# Protoboard.net
KiCad netlist of a schematic drawn in EAGLE
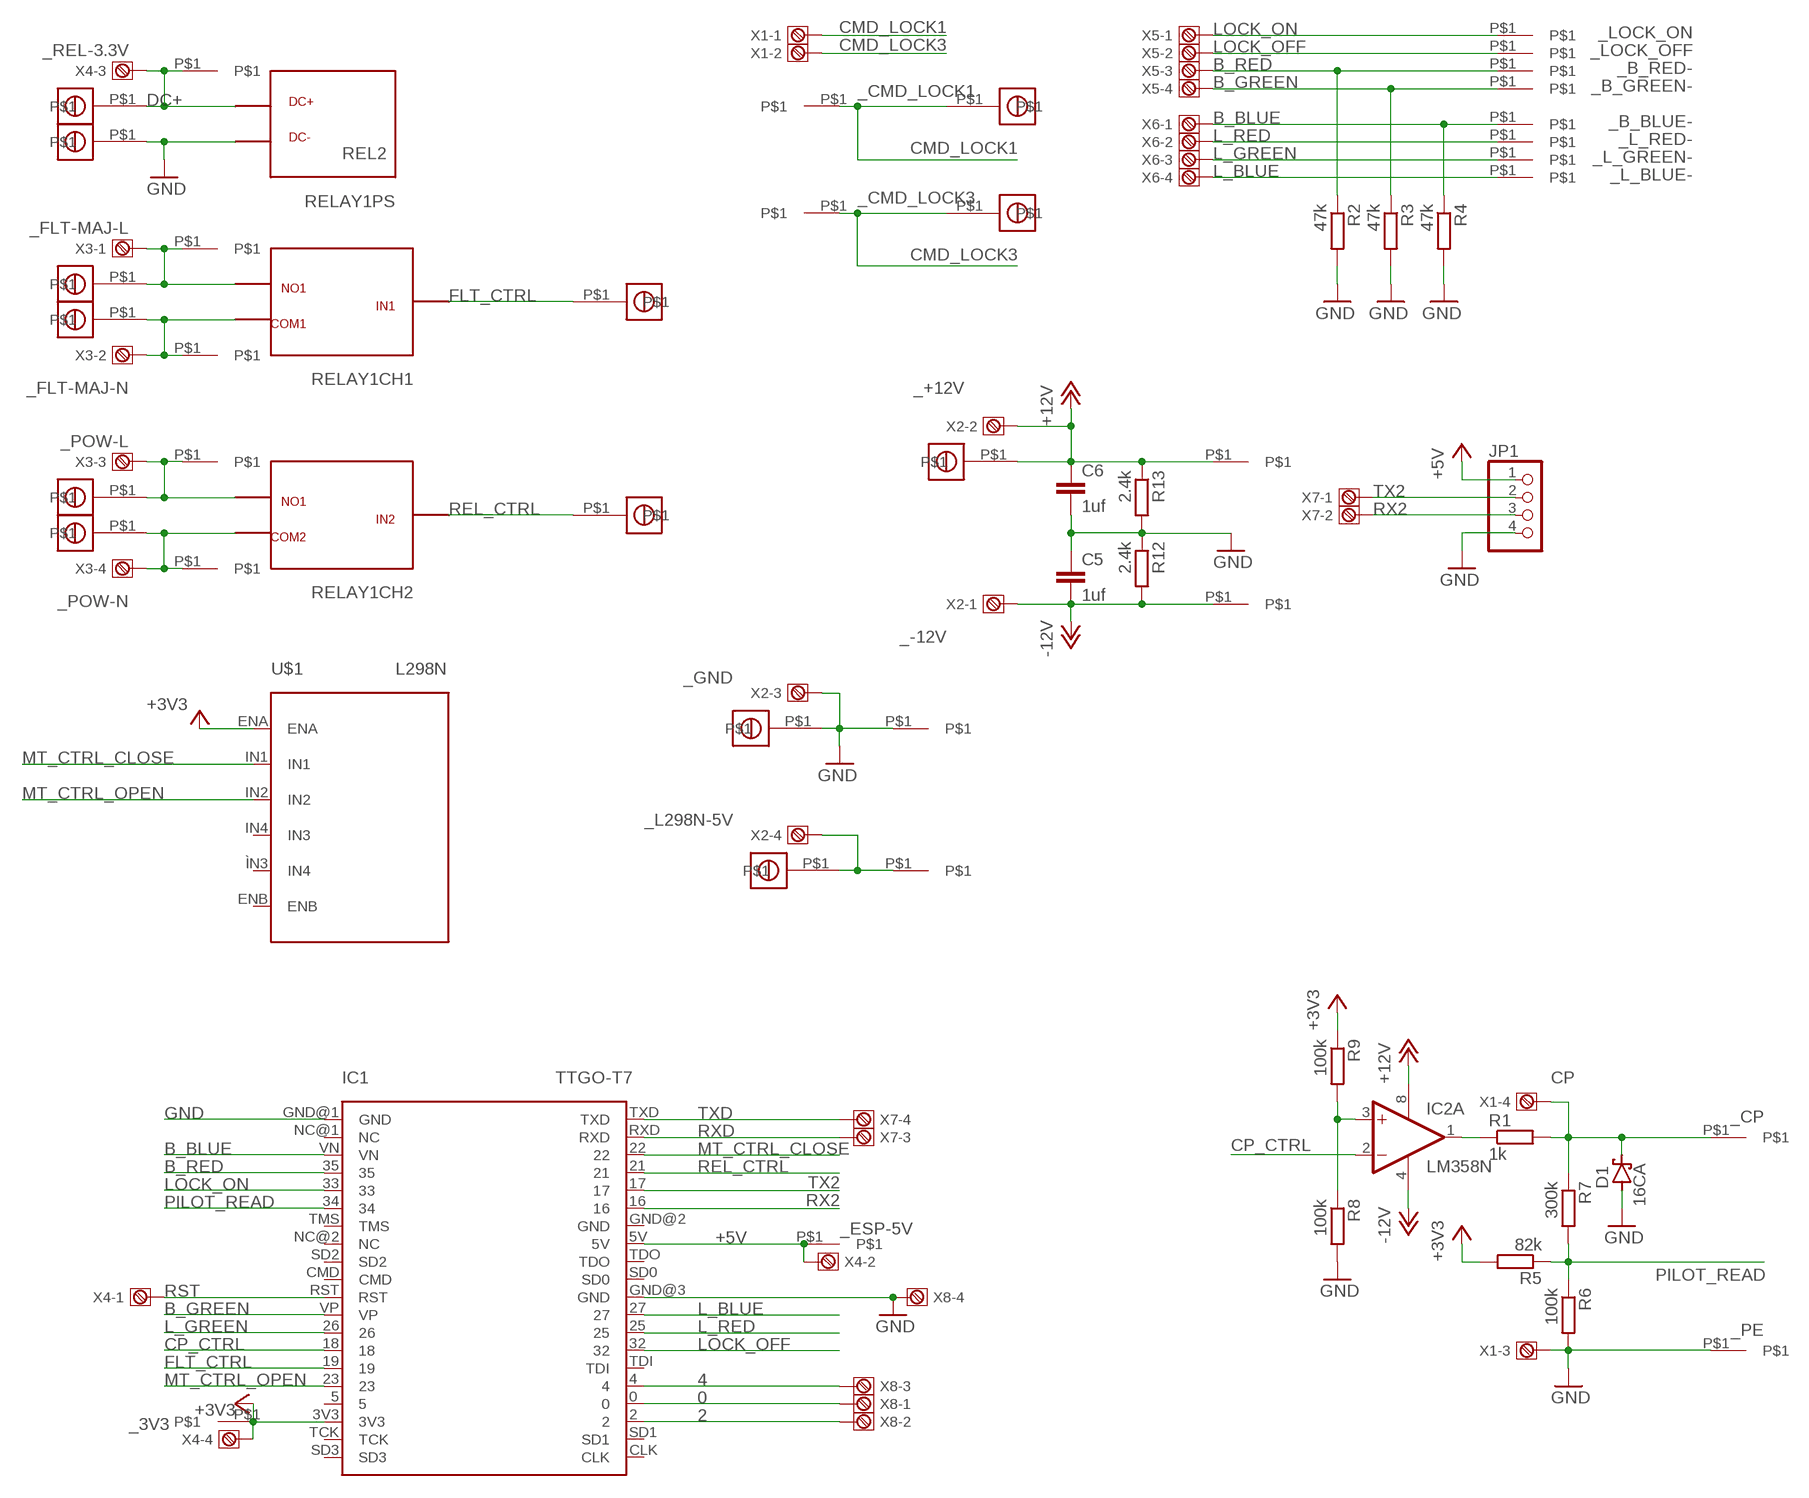
[diagram p0: schematic, sheet 1, part 1 of 2]
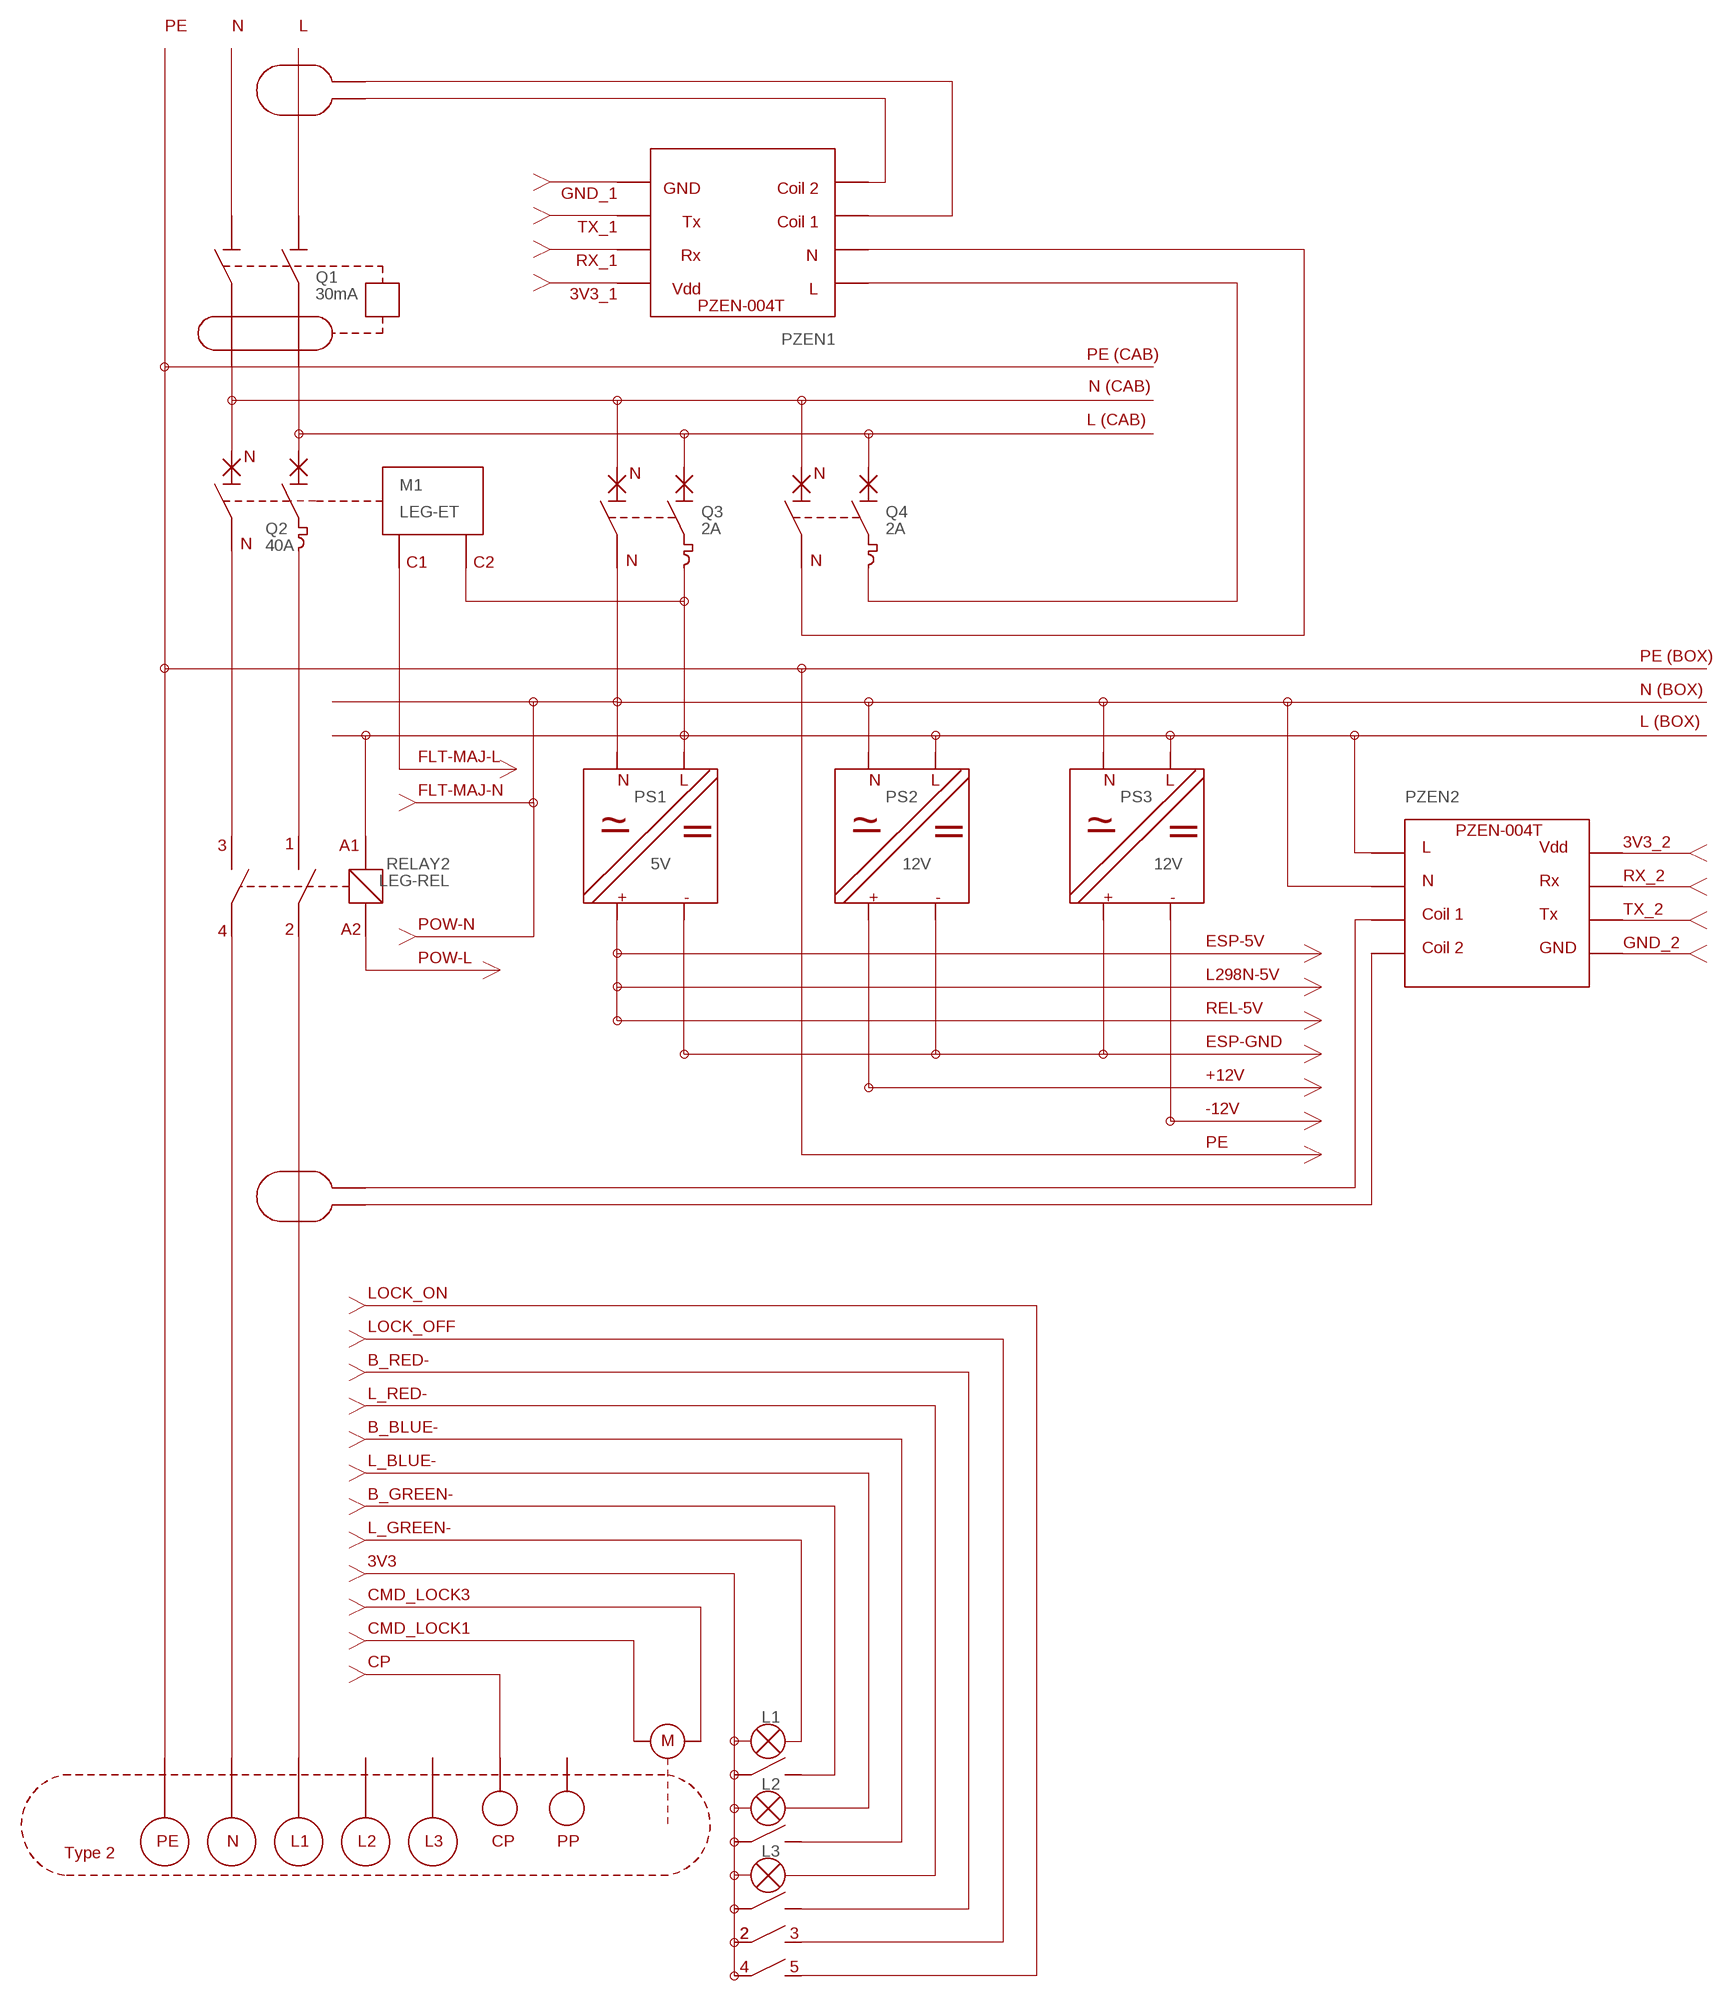
[diagram p1: schematic, sheet 1, part 2 of 2]

(export (version "E")
  (design (tool "Eeschema 10.0.6"))
  (components
    (comp (ref "5V")
      (value "BORNIER")
      (footprint "eagle-import:BORNIER")
      (libsource (lib "eagle-import") (part "BORNIER"))
    )
    (comp (ref "12V")
      (value "BORNIER")
      (footprint "eagle-import:BORNIER")
      (libsource (lib "eagle-import") (part "BORNIER"))
    )
    (comp (ref "C5")
      (value "1uf")
      (footprint "eagle-import:C050-025X075")
      (libsource (lib "eagle-import") (part "C-EU050-025X075"))
    )
    (comp (ref "C6")
      (value "1uf")
      (footprint "eagle-import:C050-025X075")
      (libsource (lib "eagle-import") (part "C-EU050-025X075"))
    )
    (comp (ref "D1")
      (value "16CA")
      (footprint "eagle-import:C1702-15")
      (libsource (lib "eagle-import") (part "P6KEXXA"))
    )
    (comp (ref "DC+")
      (value "BORNIER")
      (footprint "eagle-import:BORNIER")
      (libsource (lib "eagle-import") (part "BORNIER"))
    )
    (comp (ref "DC-")
      (value "BORNIER")
      (footprint "eagle-import:BORNIER")
      (libsource (lib "eagle-import") (part "BORNIER"))
    )
    (comp (ref "FLT-L")
      (value "BORNIER")
      (footprint "eagle-import:BORNIER")
      (libsource (lib "eagle-import") (part "BORNIER"))
    )
    (comp (ref "FLT-N")
      (value "BORNIER")
      (footprint "eagle-import:BORNIER")
      (libsource (lib "eagle-import") (part "BORNIER"))
    )
    (comp (ref "GND")
      (value "BORNIER")
      (footprint "eagle-import:BORNIER")
      (libsource (lib "eagle-import") (part "BORNIER"))
    )
    (comp (ref "IC1")
      (value "TTGO-T7")
      (footprint "eagle-import:TTGO-T7")
      (libsource (lib "eagle-import") (part "TTGO-T7"))
    )
    (comp (ref "IC2")
      (value "LM358N")
      (footprint "eagle-import:DIL08")
      (libsource (lib "eagle-import") (part "LM358N"))
    )
    (comp (ref "IN1")
      (value "BORNIER")
      (footprint "eagle-import:BORNIER")
      (libsource (lib "eagle-import") (part "BORNIER"))
    )
    (comp (ref "IN2")
      (value "BORNIER")
      (footprint "eagle-import:BORNIER")
      (libsource (lib "eagle-import") (part "BORNIER"))
    )
    (comp (ref "JP1")
      (value "PINHD-1X4")
      (footprint "eagle-import:1X04")
      (libsource (lib "eagle-import") (part "PINHD-1X4"))
    )
    (comp (ref "MT1")
      (value "BORNIER")
      (footprint "eagle-import:BORNIER")
      (libsource (lib "eagle-import") (part "BORNIER"))
    )
    (comp (ref "MT2")
      (value "BORNIER")
      (footprint "eagle-import:BORNIER")
      (libsource (lib "eagle-import") (part "BORNIER"))
    )
    (comp (ref "POW-L")
      (value "BORNIER")
      (footprint "eagle-import:BORNIER")
      (libsource (lib "eagle-import") (part "BORNIER"))
    )
    (comp (ref "POW-N")
      (value "BORNIER")
      (footprint "eagle-import:BORNIER")
      (libsource (lib "eagle-import") (part "BORNIER"))
    )
    (comp (ref "R1")
      (value "1k")
      (footprint "eagle-import:0207_10")
      (libsource (lib "eagle-import") (part "R-EU_0207/10"))
    )
    (comp (ref "R2")
      (value "47k")
      (footprint "eagle-import:0207_10")
      (libsource (lib "eagle-import") (part "R-EU_0207/10"))
    )
    (comp (ref "R3")
      (value "47k")
      (footprint "eagle-import:0207_10")
      (libsource (lib "eagle-import") (part "R-EU_0207/10"))
    )
    (comp (ref "R4")
      (value "47k")
      (footprint "eagle-import:0207_10")
      (libsource (lib "eagle-import") (part "R-EU_0207/10"))
    )
    (comp (ref "R5")
      (value "82k")
      (footprint "eagle-import:0207_10")
      (libsource (lib "eagle-import") (part "R-EU_0207/10"))
    )
    (comp (ref "R6")
      (value "100k")
      (footprint "eagle-import:0207_10")
      (libsource (lib "eagle-import") (part "R-EU_0207/10"))
    )
    (comp (ref "R7")
      (value "300k")
      (footprint "eagle-import:0207_10")
      (libsource (lib "eagle-import") (part "R-EU_0207/10"))
    )
    (comp (ref "R8")
      (value "100k")
      (footprint "eagle-import:0207_10")
      (libsource (lib "eagle-import") (part "R-EU_0207/10"))
    )
    (comp (ref "R9")
      (value "100k")
      (footprint "eagle-import:0207_10")
      (libsource (lib "eagle-import") (part "R-EU_0207/10"))
    )
    (comp (ref "R12")
      (value "2.4k")
      (footprint "eagle-import:0207_10")
      (libsource (lib "eagle-import") (part "R-EU_0207/10"))
    )
    (comp (ref "R13")
      (value "2.4k")
      (footprint "eagle-import:0207_10")
      (libsource (lib "eagle-import") (part "R-EU_0207/10"))
    )
    (comp (ref "RELAY1")
      (value "REL2")
      (footprint "eagle-import:REL2")
      (libsource (lib "eagle-import") (part "REL2"))
    )
    (comp (ref "U$1")
      (value "L298N")
      (footprint "eagle-import:L298N")
      (libsource (lib "eagle-import") (part "L298N"))
    )
    (comp (ref "X1")
      (value "1727036")
      (footprint "eagle-import:1727036")
      (fields (field (name "MF") "FARNELL"))
      (libsource (lib "eagle-import") (part "1727036"))
    )
    (comp (ref "X2")
      (value "1727036")
      (footprint "eagle-import:1727036")
      (fields (field (name "MF") "FARNELL"))
      (libsource (lib "eagle-import") (part "1727036"))
    )
    (comp (ref "X3")
      (value "1727036")
      (footprint "eagle-import:1727036")
      (fields (field (name "MF") "FARNELL"))
      (libsource (lib "eagle-import") (part "1727036"))
    )
    (comp (ref "X4")
      (value "1727036")
      (footprint "eagle-import:1727036")
      (fields (field (name "MF") "FARNELL"))
      (libsource (lib "eagle-import") (part "1727036"))
    )
    (comp (ref "X5")
      (value "1727036")
      (footprint "eagle-import:1727036")
      (fields (field (name "MF") "FARNELL"))
      (libsource (lib "eagle-import") (part "1727036"))
    )
    (comp (ref "X6")
      (value "1727036")
      (footprint "eagle-import:1727036")
      (fields (field (name "MF") "FARNELL"))
      (libsource (lib "eagle-import") (part "1727036"))
    )
    (comp (ref "X7")
      (value "1727036")
      (footprint "eagle-import:1727036")
      (fields (field (name "MF") "FARNELL"))
      (libsource (lib "eagle-import") (part "1727036"))
    )
    (comp (ref "X8")
      (value "1727036")
      (footprint "eagle-import:1727036")
      (fields (field (name "MF") "FARNELL"))
      (libsource (lib "eagle-import") (part "1727036"))
    )
    (comp (ref "_+12V")
      (value "PIN")
      (footprint "eagle-import:PIN")
      (libsource (lib "eagle-import") (part "PIN"))
    )
    (comp (ref "_-12V")
      (value "PIN")
      (footprint "eagle-import:PIN")
      (libsource (lib "eagle-import") (part "PIN"))
    )
    (comp (ref "_3V3")
      (value "PIN")
      (footprint "eagle-import:PIN")
      (libsource (lib "eagle-import") (part "PIN"))
    )
    (comp (ref "_B_BLUE-")
      (value "PIN")
      (footprint "eagle-import:PIN")
      (libsource (lib "eagle-import") (part "PIN"))
    )
    (comp (ref "_B_GREEN-")
      (value "PIN")
      (footprint "eagle-import:PIN")
      (libsource (lib "eagle-import") (part "PIN"))
    )
    (comp (ref "_B_RED-")
      (value "PIN")
      (footprint "eagle-import:PIN")
      (libsource (lib "eagle-import") (part "PIN"))
    )
    (comp (ref "_CMD_LOCK1")
      (value "PIN")
      (footprint "eagle-import:PIN")
      (libsource (lib "eagle-import") (part "PIN"))
    )
    (comp (ref "_CMD_LOCK3")
      (value "PIN")
      (footprint "eagle-import:PIN")
      (libsource (lib "eagle-import") (part "PIN"))
    )
    (comp (ref "_CP")
      (value "PIN")
      (footprint "eagle-import:PIN")
      (libsource (lib "eagle-import") (part "PIN"))
    )
    (comp (ref "_ESP-5V")
      (value "PIN")
      (footprint "eagle-import:PIN")
      (libsource (lib "eagle-import") (part "PIN"))
    )
    (comp (ref "_FLT-MAJ-L")
      (value "PIN")
      (footprint "eagle-import:PIN")
      (libsource (lib "eagle-import") (part "PIN"))
    )
    (comp (ref "_FLT-MAJ-N")
      (value "PIN")
      (footprint "eagle-import:PIN")
      (libsource (lib "eagle-import") (part "PIN"))
    )
    (comp (ref "_GND")
      (value "PIN")
      (footprint "eagle-import:PIN")
      (libsource (lib "eagle-import") (part "PIN"))
    )
    (comp (ref "_L298N-5V")
      (value "PIN")
      (footprint "eagle-import:PIN")
      (libsource (lib "eagle-import") (part "PIN"))
    )
    (comp (ref "_LOCK_OFF")
      (value "PIN")
      (footprint "eagle-import:PIN")
      (libsource (lib "eagle-import") (part "PIN"))
    )
    (comp (ref "_LOCK_ON")
      (value "PIN")
      (footprint "eagle-import:PIN")
      (libsource (lib "eagle-import") (part "PIN"))
    )
    (comp (ref "_L_BLUE-")
      (value "PIN")
      (footprint "eagle-import:PIN")
      (libsource (lib "eagle-import") (part "PIN"))
    )
    (comp (ref "_L_GREEN-")
      (value "PIN")
      (footprint "eagle-import:PIN")
      (libsource (lib "eagle-import") (part "PIN"))
    )
    (comp (ref "_L_RED-")
      (value "PIN")
      (footprint "eagle-import:PIN")
      (libsource (lib "eagle-import") (part "PIN"))
    )
    (comp (ref "_PE")
      (value "PIN")
      (footprint "eagle-import:PIN")
      (libsource (lib "eagle-import") (part "PIN"))
    )
    (comp (ref "_POW-L")
      (value "PIN")
      (footprint "eagle-import:PIN")
      (libsource (lib "eagle-import") (part "PIN"))
    )
    (comp (ref "_POW-N")
      (value "PIN")
      (footprint "eagle-import:PIN")
      (libsource (lib "eagle-import") (part "PIN"))
    )
    (comp (ref "_REL-3.3V")
      (value "PIN")
      (footprint "eagle-import:PIN")
      (libsource (lib "eagle-import") (part "PIN"))
    )
  )
  (nets
    (net (code "1") (name "+3V3") (class "Default")
      (node (ref "IC1") (pin "3V3") (pinfunction "3V3_3V3") (pintype "bidirectional"))
      (node (ref "R5") (pin "2") (pinfunction "2_2") (pintype "passive"))
      (node (ref "R9") (pin "1") (pinfunction "1_1") (pintype "passive"))
      (node (ref "U$1") (pin "ENA") (pinfunction "ENA_ENA") (pintype "bidirectional"))
      (node (ref "X4") (pin "4") (pinfunction "1_4") (pintype "passive"))
      (node (ref "_3V3") (pin "P$1") (pinfunction "P$1_P$1") (pintype "bidirectional"))
    )
    (net (code "2") (name "+5V") (class "Default")
      (node (ref "IC1") (pin "5V") (pinfunction "5V_5V") (pintype "bidirectional"))
      (node (ref "JP1") (pin "1") (pinfunction "1_1") (pintype "passive"))
      (node (ref "X4") (pin "2") (pinfunction "1_2") (pintype "passive"))
      (node (ref "_ESP-5V") (pin "P$1") (pinfunction "P$1_P$1") (pintype "bidirectional"))
    )
    (net (code "3") (name "+12V") (class "Default")
      (node (ref "12V") (pin "P$1") (pinfunction "P$1_P$1") (pintype "bidirectional"))
      (node (ref "C6") (pin "1") (pinfunction "1_1") (pintype "passive"))
      (node (ref "IC2") (pin "8") (pinfunction "V+_8") (pintype "power_in"))
      (node (ref "R13") (pin "1") (pinfunction "1_1") (pintype "passive"))
      (node (ref "X2") (pin "2") (pinfunction "1_2") (pintype "passive"))
      (node (ref "_+12V") (pin "P$1") (pinfunction "P$1_P$1") (pintype "bidirectional"))
    )
    (net (code "4") (name "-12V") (class "Default")
      (node (ref "C5") (pin "2") (pinfunction "2_2") (pintype "passive"))
      (node (ref "IC2") (pin "4") (pinfunction "V-_4") (pintype "power_in"))
      (node (ref "R12") (pin "2") (pinfunction "2_2") (pintype "passive"))
      (node (ref "X2") (pin "1") (pinfunction "1_1") (pintype "passive"))
      (node (ref "_-12V") (pin "P$1") (pinfunction "P$1_P$1") (pintype "bidirectional"))
    )
    (net (code "5") (name "/0") (class "Default")
      (node (ref "IC1") (pin "0") (pinfunction "0_0") (pintype "bidirectional"))
      (node (ref "X8") (pin "1") (pinfunction "1_1") (pintype "passive"))
    )
    (net (code "6") (name "/2") (class "Default")
      (node (ref "IC1") (pin "2") (pinfunction "2_2") (pintype "bidirectional"))
      (node (ref "X8") (pin "2") (pinfunction "1_2") (pintype "passive"))
    )
    (net (code "7") (name "/4") (class "Default")
      (node (ref "IC1") (pin "4") (pinfunction "4_4") (pintype "bidirectional"))
      (node (ref "X8") (pin "3") (pinfunction "1_3") (pintype "passive"))
    )
    (net (code "8") (name "/B_BLUE") (class "Default")
      (node (ref "IC1") (pin "VN") (pinfunction "VN_VN") (pintype "bidirectional"))
      (node (ref "R4") (pin "1") (pinfunction "1_1") (pintype "passive"))
      (node (ref "X6") (pin "1") (pinfunction "1_1") (pintype "passive"))
      (node (ref "_B_BLUE-") (pin "P$1") (pinfunction "P$1_P$1") (pintype "bidirectional"))
    )
    (net (code "9") (name "/B_GREEN") (class "Default")
      (node (ref "IC1") (pin "VP") (pinfunction "VP_VP") (pintype "bidirectional"))
      (node (ref "R3") (pin "1") (pinfunction "1_1") (pintype "passive"))
      (node (ref "X5") (pin "4") (pinfunction "1_4") (pintype "passive"))
      (node (ref "_B_GREEN-") (pin "P$1") (pinfunction "P$1_P$1") (pintype "bidirectional"))
    )
    (net (code "10") (name "/B_RED") (class "Default")
      (node (ref "IC1") (pin "35") (pinfunction "35_35") (pintype "bidirectional"))
      (node (ref "R2") (pin "1") (pinfunction "1_1") (pintype "passive"))
      (node (ref "X5") (pin "3") (pinfunction "1_3") (pintype "passive"))
      (node (ref "_B_RED-") (pin "P$1") (pinfunction "P$1_P$1") (pintype "bidirectional"))
    )
    (net (code "11") (name "/CMD_LOCK1") (class "Default")
      (node (ref "MT2") (pin "P$1") (pinfunction "P$1_P$1") (pintype "bidirectional"))
      (node (ref "X1") (pin "2") (pinfunction "1_2") (pintype "passive"))
      (node (ref "_CMD_LOCK1") (pin "P$1") (pinfunction "P$1_P$1") (pintype "bidirectional"))
    )
    (net (code "12") (name "/CMD_LOCK3") (class "Default")
      (node (ref "MT1") (pin "P$1") (pinfunction "P$1_P$1") (pintype "bidirectional"))
      (node (ref "X1") (pin "1") (pinfunction "1_1") (pintype "passive"))
      (node (ref "_CMD_LOCK3") (pin "P$1") (pinfunction "P$1_P$1") (pintype "bidirectional"))
    )
    (net (code "13") (name "/CP") (class "Default")
      (node (ref "D1") (pin "C") (pinfunction "C_C") (pintype "passive"))
      (node (ref "R1") (pin "2") (pinfunction "2_2") (pintype "passive"))
      (node (ref "R7") (pin "1") (pinfunction "1_1") (pintype "passive"))
      (node (ref "X1") (pin "4") (pinfunction "1_4") (pintype "passive"))
      (node (ref "_CP") (pin "P$1") (pinfunction "P$1_P$1") (pintype "bidirectional"))
    )
    (net (code "14") (name "/CP_CTRL") (class "Default")
      (node (ref "IC1") (pin "18") (pinfunction "18_18") (pintype "bidirectional"))
      (node (ref "IC2") (pin "2") (pinfunction "-IN_2") (pintype "input"))
    )
    (net (code "15") (name "/DC+") (class "Default")
      (node (ref "DC+") (pin "P$1") (pinfunction "P$1_P$1") (pintype "bidirectional"))
      (node (ref "X4") (pin "3") (pinfunction "1_3") (pintype "passive"))
      (node (ref "_REL-3.3V") (pin "P$1") (pinfunction "P$1_P$1") (pintype "bidirectional"))
    )
    (net (code "16") (name "/FLT_CTRL") (class "Default")
      (node (ref "IC1") (pin "19") (pinfunction "19_19") (pintype "bidirectional"))
      (node (ref "IN1") (pin "P$1") (pinfunction "P$1_P$1") (pintype "bidirectional"))
    )
    (net (code "17") (name "/LOCK_OFF") (class "Default")
      (node (ref "IC1") (pin "32") (pinfunction "32_32") (pintype "bidirectional"))
      (node (ref "X5") (pin "2") (pinfunction "1_2") (pintype "passive"))
      (node (ref "_LOCK_OFF") (pin "P$1") (pinfunction "P$1_P$1") (pintype "bidirectional"))
    )
    (net (code "18") (name "/LOCK_ON") (class "Default")
      (node (ref "IC1") (pin "33") (pinfunction "33_33") (pintype "bidirectional"))
      (node (ref "X5") (pin "1") (pinfunction "1_1") (pintype "passive"))
      (node (ref "_LOCK_ON") (pin "P$1") (pinfunction "P$1_P$1") (pintype "bidirectional"))
    )
    (net (code "19") (name "/L_BLUE") (class "Default")
      (node (ref "IC1") (pin "27") (pinfunction "27_27") (pintype "bidirectional"))
      (node (ref "X6") (pin "4") (pinfunction "1_4") (pintype "passive"))
      (node (ref "_L_BLUE-") (pin "P$1") (pinfunction "P$1_P$1") (pintype "bidirectional"))
    )
    (net (code "20") (name "/L_GREEN") (class "Default")
      (node (ref "IC1") (pin "26") (pinfunction "26_26") (pintype "bidirectional"))
      (node (ref "X6") (pin "3") (pinfunction "1_3") (pintype "passive"))
      (node (ref "_L_GREEN-") (pin "P$1") (pinfunction "P$1_P$1") (pintype "bidirectional"))
    )
    (net (code "21") (name "/L_RED") (class "Default")
      (node (ref "IC1") (pin "25") (pinfunction "25_25") (pintype "bidirectional"))
      (node (ref "X6") (pin "2") (pinfunction "1_2") (pintype "passive"))
      (node (ref "_L_RED-") (pin "P$1") (pinfunction "P$1_P$1") (pintype "bidirectional"))
    )
    (net (code "22") (name "/MT_CTRL_CLOSE") (class "Default")
      (node (ref "IC1") (pin "22") (pinfunction "22_22") (pintype "bidirectional"))
      (node (ref "U$1") (pin "IN1") (pinfunction "IN1_IN1") (pintype "bidirectional"))
    )
    (net (code "23") (name "/MT_CTRL_OPEN") (class "Default")
      (node (ref "IC1") (pin "23") (pinfunction "23_23") (pintype "bidirectional"))
      (node (ref "U$1") (pin "IN2") (pinfunction "IN2_IN2") (pintype "bidirectional"))
    )
    (net (code "24") (name "/PILOT_READ") (class "Default")
      (node (ref "IC1") (pin "34") (pinfunction "34_34") (pintype "bidirectional"))
      (node (ref "R5") (pin "1") (pinfunction "1_1") (pintype "passive"))
      (node (ref "R6") (pin "1") (pinfunction "1_1") (pintype "passive"))
      (node (ref "R7") (pin "2") (pinfunction "2_2") (pintype "passive"))
    )
    (net (code "25") (name "/REL_CTRL") (class "Default")
      (node (ref "IC1") (pin "21") (pinfunction "21_21") (pintype "bidirectional"))
      (node (ref "IN2") (pin "P$1") (pinfunction "P$1_P$1") (pintype "bidirectional"))
    )
    (net (code "26") (name "/RST") (class "Default")
      (node (ref "IC1") (pin "RST") (pinfunction "RST_RST") (pintype "bidirectional"))
      (node (ref "X4") (pin "1") (pinfunction "1_1") (pintype "passive"))
    )
    (net (code "27") (name "/RX2") (class "Default")
      (node (ref "IC1") (pin "16") (pinfunction "16_16") (pintype "bidirectional"))
      (node (ref "JP1") (pin "3") (pinfunction "3_3") (pintype "passive"))
      (node (ref "X7") (pin "2") (pinfunction "1_2") (pintype "passive"))
    )
    (net (code "28") (name "/RXD") (class "Default")
      (node (ref "IC1") (pin "RXD") (pinfunction "RXD_RXD") (pintype "bidirectional"))
      (node (ref "X7") (pin "3") (pinfunction "1_3") (pintype "passive"))
    )
    (net (code "29") (name "/TX2") (class "Default")
      (node (ref "IC1") (pin "17") (pinfunction "17_17") (pintype "bidirectional"))
      (node (ref "JP1") (pin "2") (pinfunction "2_2") (pintype "passive"))
      (node (ref "X7") (pin "1") (pinfunction "1_1") (pintype "passive"))
    )
    (net (code "30") (name "/TXD") (class "Default")
      (node (ref "IC1") (pin "TXD") (pinfunction "TXD_TXD") (pintype "bidirectional"))
      (node (ref "X7") (pin "4") (pinfunction "1_4") (pintype "passive"))
    )
    (net (code "31") (name "GND") (class "Default")
      (node (ref "C5") (pin "1") (pinfunction "1_1") (pintype "passive"))
      (node (ref "C6") (pin "2") (pinfunction "2_2") (pintype "passive"))
      (node (ref "D1") (pin "A") (pinfunction "A_A") (pintype "passive"))
      (node (ref "DC-") (pin "P$1") (pinfunction "P$1_P$1") (pintype "bidirectional"))
      (node (ref "GND") (pin "P$1") (pinfunction "P$1_P$1") (pintype "bidirectional"))
      (node (ref "IC1") (pin "GND@1") (pinfunction "GND_GND@1") (pintype "bidirectional"))
      (node (ref "IC1") (pin "GND@3") (pinfunction "GND_GND@3") (pintype "bidirectional"))
      (node (ref "JP1") (pin "4") (pinfunction "4_4") (pintype "passive"))
      (node (ref "R12") (pin "1") (pinfunction "1_1") (pintype "passive"))
      (node (ref "R13") (pin "2") (pinfunction "2_2") (pintype "passive"))
      (node (ref "R2") (pin "2") (pinfunction "2_2") (pintype "passive"))
      (node (ref "R3") (pin "2") (pinfunction "2_2") (pintype "passive"))
      (node (ref "R4") (pin "2") (pinfunction "2_2") (pintype "passive"))
      (node (ref "R6") (pin "2") (pinfunction "2_2") (pintype "passive"))
      (node (ref "R8") (pin "2") (pinfunction "2_2") (pintype "passive"))
      (node (ref "X1") (pin "3") (pinfunction "1_3") (pintype "passive"))
      (node (ref "X2") (pin "3") (pinfunction "1_3") (pintype "passive"))
      (node (ref "X8") (pin "4") (pinfunction "1_4") (pintype "passive"))
      (node (ref "_GND") (pin "P$1") (pinfunction "P$1_P$1") (pintype "bidirectional"))
      (node (ref "_PE") (pin "P$1") (pinfunction "P$1_P$1") (pintype "bidirectional"))
    )
    (net (code "32") (name "Net-(FLT-L-PadP$1)") (class "Default")
      (node (ref "FLT-L") (pin "P$1") (pinfunction "P$1_P$1") (pintype "bidirectional"))
      (node (ref "X3") (pin "1") (pinfunction "1_1") (pintype "passive"))
      (node (ref "_FLT-MAJ-L") (pin "P$1") (pinfunction "P$1_P$1") (pintype "bidirectional"))
    )
    (net (code "33") (name "Net-(IC2A-+IN)") (class "Default")
      (node (ref "IC2") (pin "3") (pinfunction "+IN_3") (pintype "input"))
      (node (ref "R8") (pin "1") (pinfunction "1_1") (pintype "passive"))
      (node (ref "R9") (pin "2") (pinfunction "2_2") (pintype "passive"))
    )
    (net (code "34") (name "Net-(IC2A-OUT)") (class "Default")
      (node (ref "IC2") (pin "1") (pinfunction "OUT_1") (pintype "output"))
      (node (ref "R1") (pin "1") (pinfunction "1_1") (pintype "passive"))
    )
    (net (code "35") (name "Net-(X2D-1)") (class "Default")
      (node (ref "5V") (pin "P$1") (pinfunction "P$1_P$1") (pintype "bidirectional"))
      (node (ref "X2") (pin "4") (pinfunction "1_4") (pintype "passive"))
      (node (ref "_L298N-5V") (pin "P$1") (pinfunction "P$1_P$1") (pintype "bidirectional"))
    )
    (net (code "36") (name "Net-(X3B-1)") (class "Default")
      (node (ref "FLT-N") (pin "P$1") (pinfunction "P$1_P$1") (pintype "bidirectional"))
      (node (ref "X3") (pin "2") (pinfunction "1_2") (pintype "passive"))
      (node (ref "_FLT-MAJ-N") (pin "P$1") (pinfunction "P$1_P$1") (pintype "bidirectional"))
    )
    (net (code "37") (name "Net-(X3C-1)") (class "Default")
      (node (ref "POW-L") (pin "P$1") (pinfunction "P$1_P$1") (pintype "bidirectional"))
      (node (ref "X3") (pin "3") (pinfunction "1_3") (pintype "passive"))
      (node (ref "_POW-L") (pin "P$1") (pinfunction "P$1_P$1") (pintype "bidirectional"))
    )
    (net (code "38") (name "Net-(X3D-1)") (class "Default")
      (node (ref "POW-N") (pin "P$1") (pinfunction "P$1_P$1") (pintype "bidirectional"))
      (node (ref "X3") (pin "4") (pinfunction "1_4") (pintype "passive"))
      (node (ref "_POW-N") (pin "P$1") (pinfunction "P$1_P$1") (pintype "bidirectional"))
    )
    (net (code "39") (name "unconnected-(IC1-GND-PadGND@2)") (class "Default")
      (node (ref "IC1") (pin "GND@2") (pinfunction "GND_GND@2") (pintype "bidirectional"))
    )
    (net (code "40") (name "unconnected-(IC1-NC-PadNC@1)") (class "Default")
      (node (ref "IC1") (pin "NC@1") (pinfunction "NC_NC@1") (pintype "bidirectional"))
    )
    (net (code "41") (name "unconnected-(IC1-NC-PadNC@2)") (class "Default")
      (node (ref "IC1") (pin "NC@2") (pinfunction "NC_NC@2") (pintype "bidirectional"))
    )
    (net (code "42") (name "unconnected-(IC1-Pad5)") (class "Default")
      (node (ref "IC1") (pin "5") (pinfunction "5_5") (pintype "bidirectional"))
    )
    (net (code "43") (name "unconnected-(IC1-PadCLK)") (class "Default")
      (node (ref "IC1") (pin "CLK") (pinfunction "CLK_CLK") (pintype "bidirectional"))
    )
    (net (code "44") (name "unconnected-(IC1-PadCMD)") (class "Default")
      (node (ref "IC1") (pin "CMD") (pinfunction "CMD_CMD") (pintype "bidirectional"))
    )
    (net (code "45") (name "unconnected-(IC1-PadSD0)") (class "Default")
      (node (ref "IC1") (pin "SD0") (pinfunction "SD0_SD0") (pintype "bidirectional"))
    )
    (net (code "46") (name "unconnected-(IC1-PadSD1)") (class "Default")
      (node (ref "IC1") (pin "SD1") (pinfunction "SD1_SD1") (pintype "bidirectional"))
    )
    (net (code "47") (name "unconnected-(IC1-PadSD2)") (class "Default")
      (node (ref "IC1") (pin "SD2") (pinfunction "SD2_SD2") (pintype "bidirectional"))
    )
    (net (code "48") (name "unconnected-(IC1-PadSD3)") (class "Default")
      (node (ref "IC1") (pin "SD3") (pinfunction "SD3_SD3") (pintype "bidirectional"))
    )
    (net (code "49") (name "unconnected-(IC1-PadTCK)") (class "Default")
      (node (ref "IC1") (pin "TCK") (pinfunction "TCK_TCK") (pintype "bidirectional"))
    )
    (net (code "50") (name "unconnected-(IC1-PadTDI)") (class "Default")
      (node (ref "IC1") (pin "TDI") (pinfunction "TDI_TDI") (pintype "bidirectional"))
    )
    (net (code "51") (name "unconnected-(IC1-PadTDO)") (class "Default")
      (node (ref "IC1") (pin "TDO") (pinfunction "TDO_TDO") (pintype "bidirectional"))
    )
    (net (code "52") (name "unconnected-(IC1-PadTMS)") (class "Default")
      (node (ref "IC1") (pin "TMS") (pinfunction "TMS_TMS") (pintype "bidirectional"))
    )
    (net (code "53") (name "unconnected-(U$1-IN3-PadIN4)") (class "Default")
      (node (ref "U$1") (pin "IN4") (pinfunction "IN3_IN4") (pintype "bidirectional"))
    )
    (net (code "54") (name "unconnected-(U$1-IN4-PadÌN3)") (class "Default")
      (node (ref "U$1") (pin "ÌN3") (pinfunction "IN4_ÌN3") (pintype "bidirectional"))
    )
    (net (code "55") (name "unconnected-(U$1-PadENB)") (class "Default")
      (node (ref "U$1") (pin "ENB") (pinfunction "ENB_ENB") (pintype "bidirectional"))
    )
  )
)
